# btretro_main.net
KiCad netlist of a schematic drawn in Altium Designer
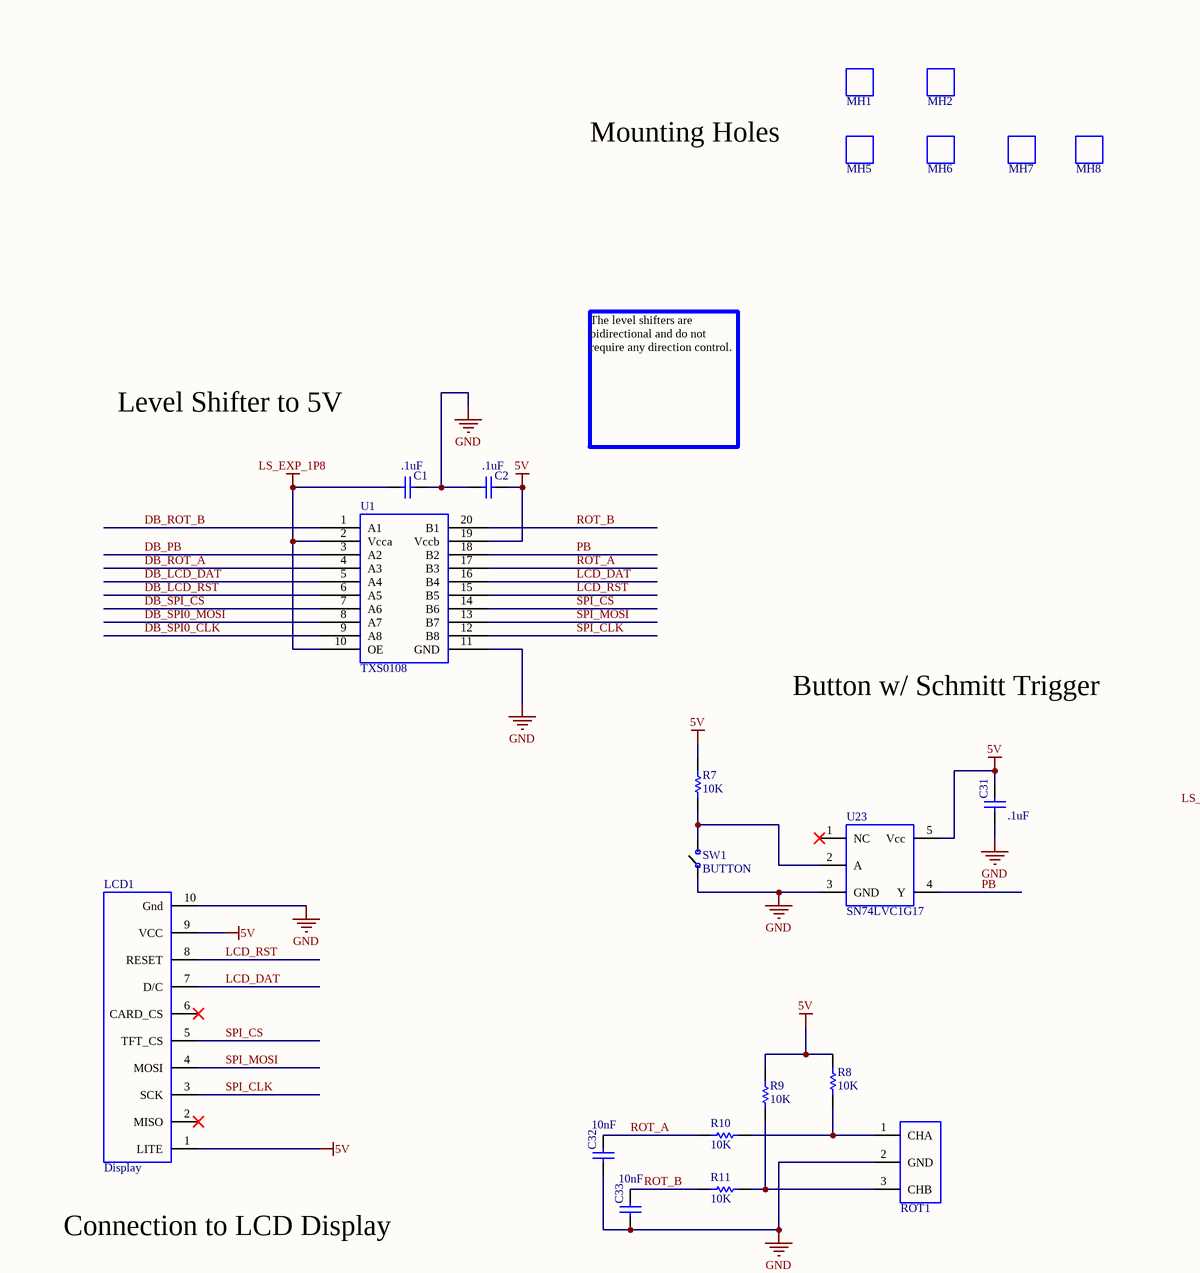
[diagram p0: btretro_main.SchDoc, top left]
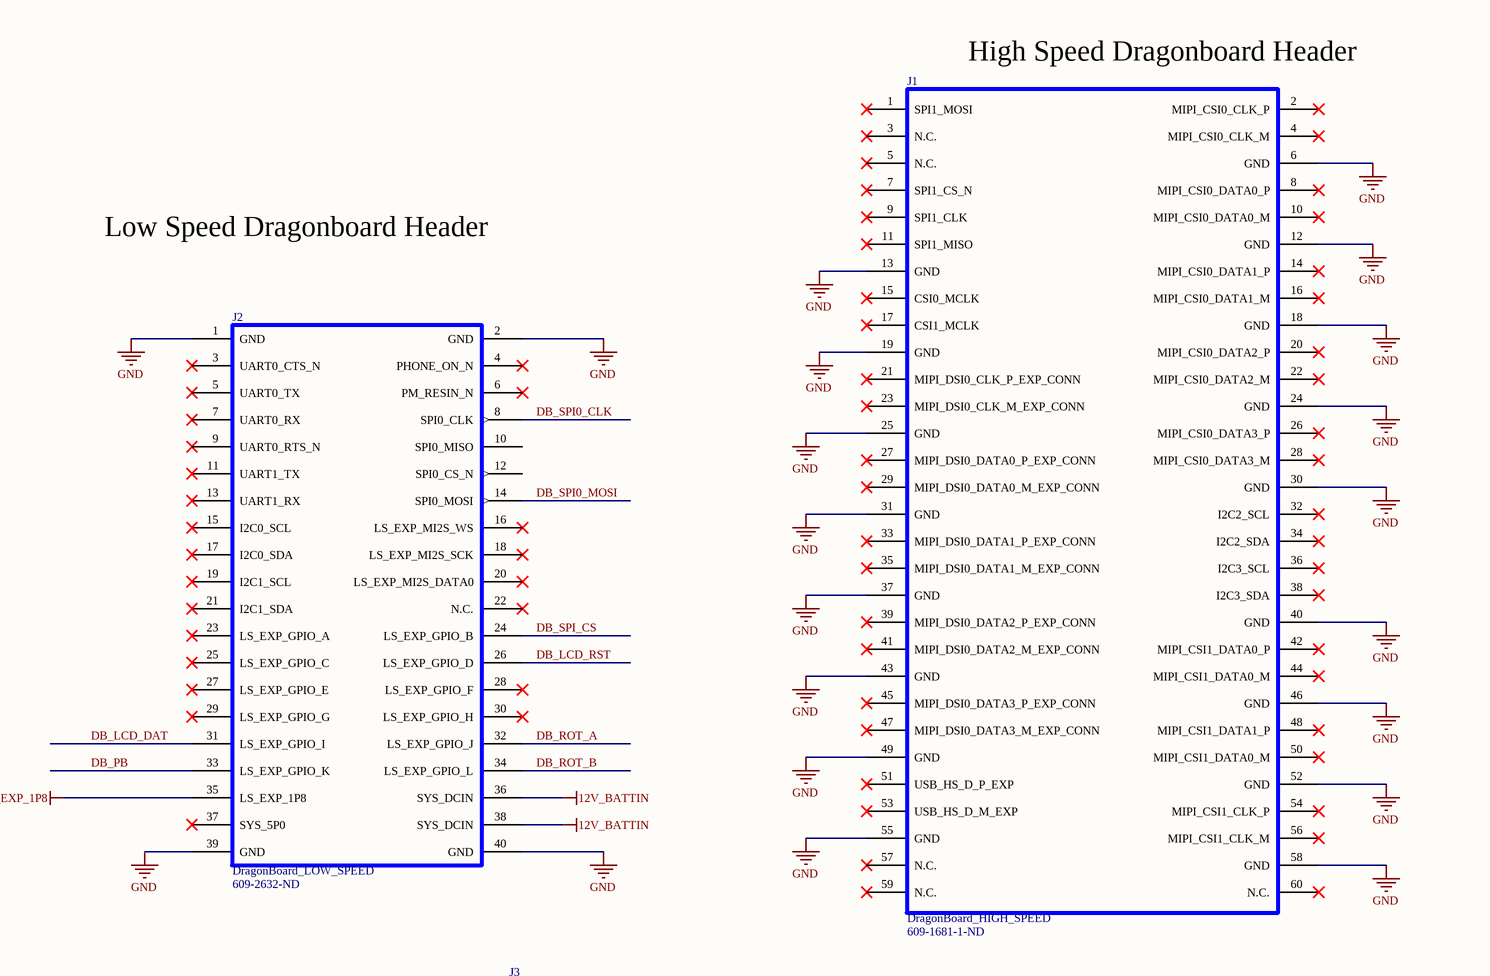
[diagram p1: btretro_main.SchDoc, top right]
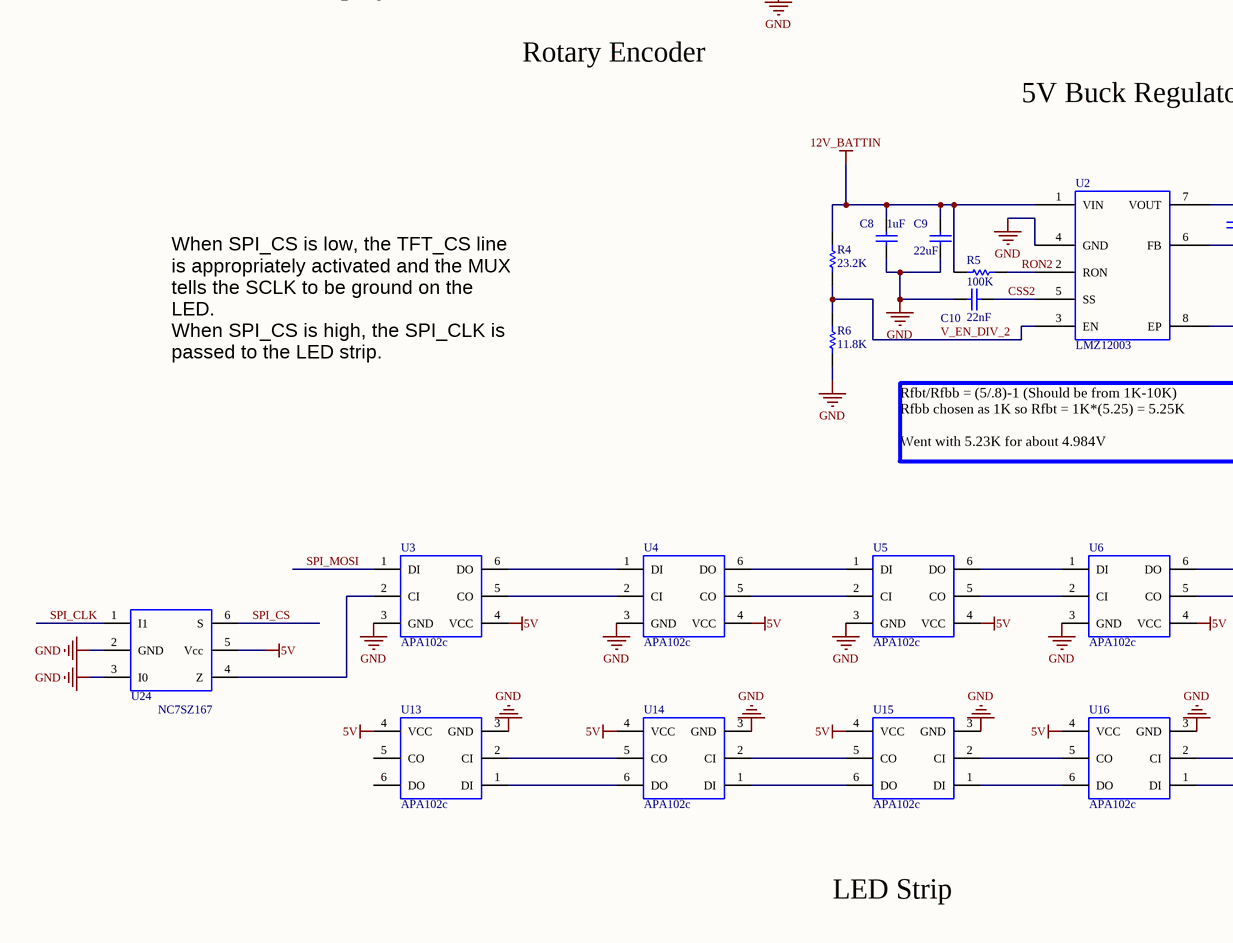
[diagram p2: btretro_main.SchDoc, bottom left]
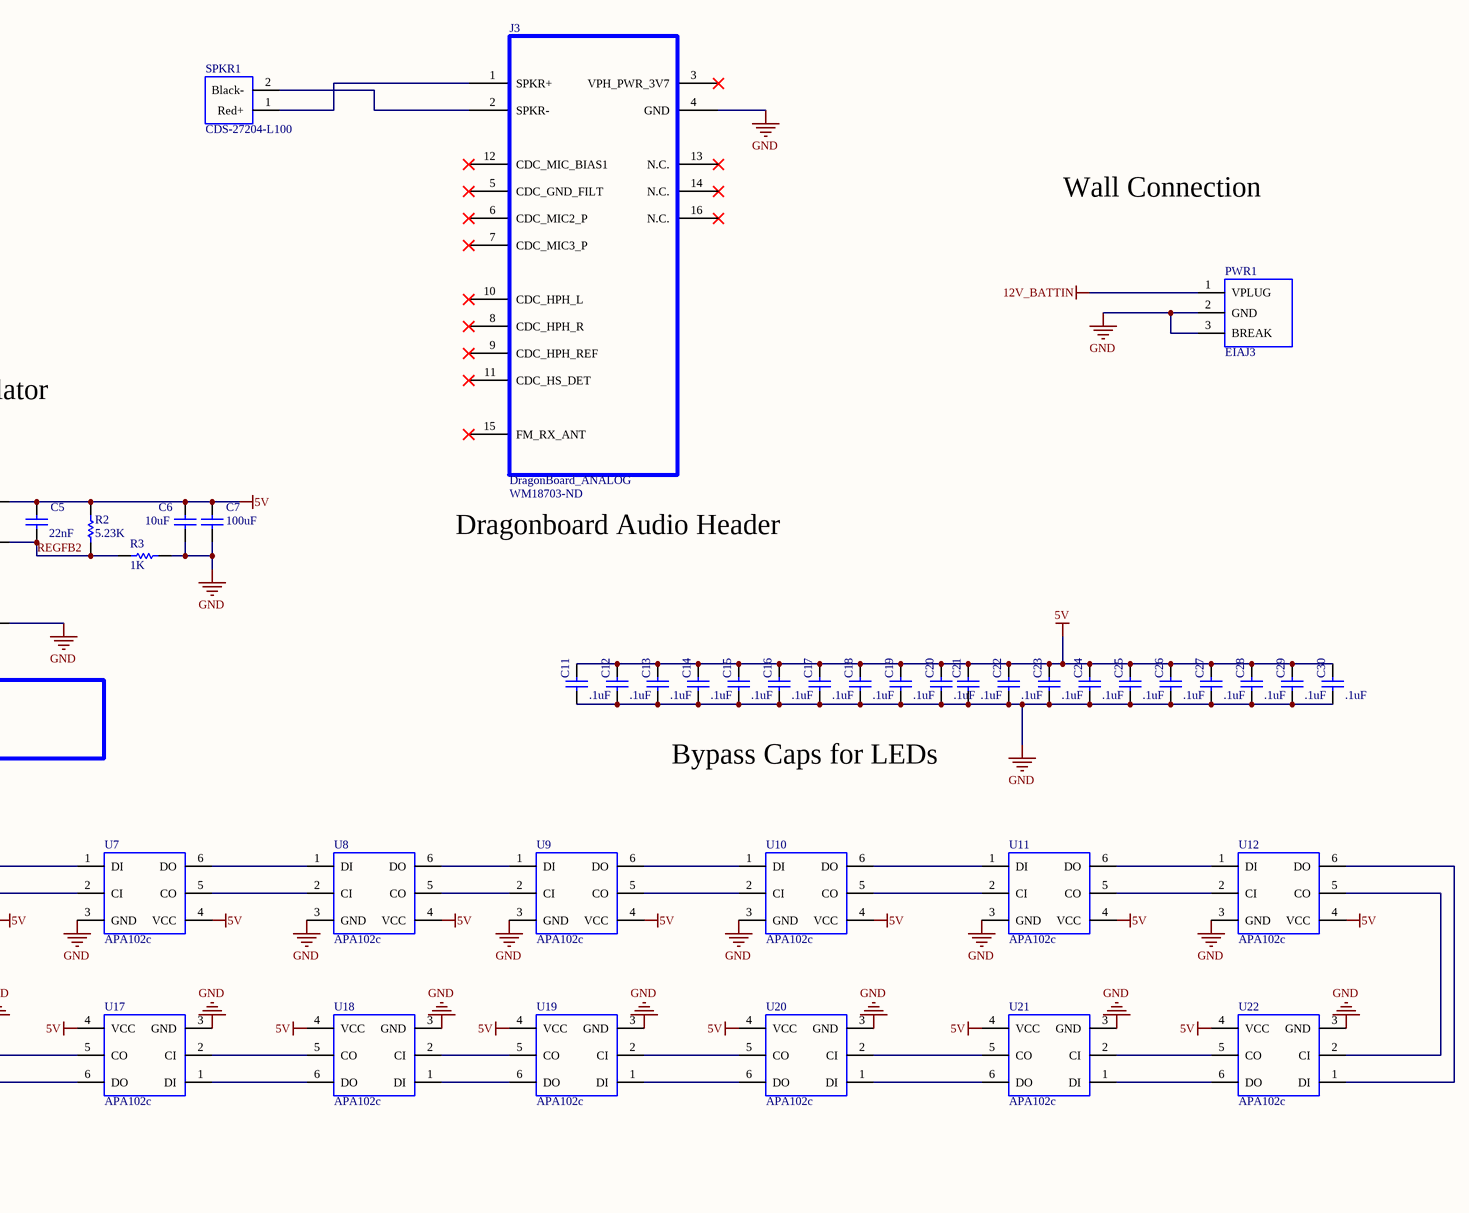
[diagram p3: btretro_main.SchDoc, bottom right]

(export (version "E")
  (design (tool "Eeschema 10.0.6"))
  (components
    (comp (ref "C1")
      (value ".1uF")
      (footprint "CAPC2012X135N")
      (description "Cap Ceramic 0.1uF 250V X7T 10% SMD 0805 125C Plastic T/R")
      (fields
        (field (name "MANUFACTURER") "TDK")
        (field (name "MANUFACTURER PART NUMBER") "C2012X7T2E104K125AE")
      )
      (libsource (lib "schlib_truman") (part "CAP_0805_.1u_250V"))
    )
    (comp (ref "C2")
      (value ".1uF")
      (footprint "CAPC2012X135N")
      (description "Cap Ceramic 0.1uF 250V X7T 10% SMD 0805 125C Plastic T/R")
      (fields
        (field (name "MANUFACTURER") "TDK")
        (field (name "MANUFACTURER PART NUMBER") "C2012X7T2E104K125AE")
      )
      (libsource (lib "schlib_truman") (part "CAP_0805_.1u_250V"))
    )
    (comp (ref "C5")
      (value "22nF")
      (footprint "CAPC2012X135N")
      (description "CAP CER 0.022UF 100V X7R 0805")
      (fields
        (field (name "MANUFACTURER") "TDK")
        (field (name "MANUFACTURER PART NUMBER") "CGJ4J2X7R2A223K125AA")
      )
      (libsource (lib "schlib_truman") (part "CAP_0805_22n_100V"))
    )
    (comp (ref "C6")
      (value "10uF")
      (footprint "CAPC2012X135N")
      (description "Cap Ceramic 10uF 16V X5R 10% SMD 0805 85C T/R")
      (fields
        (field (name "MANUFACTURER") "Johanson Dielectrics")
        (field (name "MANUFACTURER PART NUMBER") "160R15X106KV4E")
      )
      (libsource (lib "schlib_truman") (part "CAP_0805_10u_16V"))
    )
    (comp (ref "C7")
      (value "100uF")
      (footprint "FP_1210")
      (description "Cap Ceramic 100uF 10V X5R 20% SMD 1210 85C Embossed T/R")
      (fields
        (field (name "MANUFACTURER") "Murata")
        (field (name "MANUFACTURER PART NUMBER") "GRM32ER61A107ME20L")
      )
      (libsource (lib "schlib_truman") (part "CAP_1210_100u_10V"))
    )
    (comp (ref "C8")
      (value "1uF")
      (footprint "CAPC2012X135N")
      (description "CAP CER 1UF 100V X7S 0805")
      (fields
        (field (name "MANUFACTURER") "TDK")
        (field (name "MANUFACTURER PART NUMBER") "C2012X7S2A105K125AE")
      )
      (libsource (lib "schlib_truman") (part "CAP_0805_1u_100V"))
    )
    (comp (ref "C9")
      (value "22uF")
      (footprint "CAPC2012X135N")
      (fields
        (field (name "MANUFACTURER") "Samsung")
        (field (name "MANUFACTURER PART NUMBER") "CL21A226MAQNNNE")
        (field (name "TOLERANCE") "20%")
      )
      (libsource (lib "schlib_truman") (part "CAP_0805_22u_25V"))
    )
    (comp (ref "C10")
      (value "22nF")
      (footprint "CAPC2012X135N")
      (description "CAP CER 0.022UF 100V X7R 0805")
      (fields
        (field (name "MANUFACTURER") "TDK")
        (field (name "MANUFACTURER PART NUMBER") "CGJ4J2X7R2A223K125AA")
      )
      (libsource (lib "schlib_truman") (part "CAP_0805_22n_100V"))
    )
    (comp (ref "C11")
      (value ".1uF")
      (footprint "CAPC2012X135N")
      (description "Cap Ceramic 0.1uF 250V X7T 10% SMD 0805 125C Plastic T/R")
      (fields
        (field (name "MANUFACTURER") "TDK")
        (field (name "MANUFACTURER PART NUMBER") "C2012X7T2E104K125AE")
      )
      (libsource (lib "btretro_schlib") (part "CAP_0805_.1u_250V"))
    )
    (comp (ref "C12")
      (value ".1uF")
      (footprint "CAPC2012X135N")
      (description "Cap Ceramic 0.1uF 250V X7T 10% SMD 0805 125C Plastic T/R")
      (fields
        (field (name "MANUFACTURER") "TDK")
        (field (name "MANUFACTURER PART NUMBER") "C2012X7T2E104K125AE")
      )
      (libsource (lib "btretro_schlib") (part "CAP_0805_.1u_250V"))
    )
    (comp (ref "C13")
      (value ".1uF")
      (footprint "CAPC2012X135N")
      (description "Cap Ceramic 0.1uF 250V X7T 10% SMD 0805 125C Plastic T/R")
      (fields
        (field (name "MANUFACTURER") "TDK")
        (field (name "MANUFACTURER PART NUMBER") "C2012X7T2E104K125AE")
      )
      (libsource (lib "btretro_schlib") (part "CAP_0805_.1u_250V"))
    )
    (comp (ref "C14")
      (value ".1uF")
      (footprint "CAPC2012X135N")
      (description "Cap Ceramic 0.1uF 250V X7T 10% SMD 0805 125C Plastic T/R")
      (fields
        (field (name "MANUFACTURER") "TDK")
        (field (name "MANUFACTURER PART NUMBER") "C2012X7T2E104K125AE")
      )
      (libsource (lib "btretro_schlib") (part "CAP_0805_.1u_250V"))
    )
    (comp (ref "C15")
      (value ".1uF")
      (footprint "CAPC2012X135N")
      (description "Cap Ceramic 0.1uF 250V X7T 10% SMD 0805 125C Plastic T/R")
      (fields
        (field (name "MANUFACTURER") "TDK")
        (field (name "MANUFACTURER PART NUMBER") "C2012X7T2E104K125AE")
      )
      (libsource (lib "btretro_schlib") (part "CAP_0805_.1u_250V"))
    )
    (comp (ref "C16")
      (value ".1uF")
      (footprint "CAPC2012X135N")
      (description "Cap Ceramic 0.1uF 250V X7T 10% SMD 0805 125C Plastic T/R")
      (fields
        (field (name "MANUFACTURER") "TDK")
        (field (name "MANUFACTURER PART NUMBER") "C2012X7T2E104K125AE")
      )
      (libsource (lib "btretro_schlib") (part "CAP_0805_.1u_250V"))
    )
    (comp (ref "C17")
      (value ".1uF")
      (footprint "CAPC2012X135N")
      (description "Cap Ceramic 0.1uF 250V X7T 10% SMD 0805 125C Plastic T/R")
      (fields
        (field (name "MANUFACTURER") "TDK")
        (field (name "MANUFACTURER PART NUMBER") "C2012X7T2E104K125AE")
      )
      (libsource (lib "btretro_schlib") (part "CAP_0805_.1u_250V"))
    )
    (comp (ref "C18")
      (value ".1uF")
      (footprint "CAPC2012X135N")
      (description "Cap Ceramic 0.1uF 250V X7T 10% SMD 0805 125C Plastic T/R")
      (fields
        (field (name "MANUFACTURER") "TDK")
        (field (name "MANUFACTURER PART NUMBER") "C2012X7T2E104K125AE")
      )
      (libsource (lib "btretro_schlib") (part "CAP_0805_.1u_250V"))
    )
    (comp (ref "C19")
      (value ".1uF")
      (footprint "CAPC2012X135N")
      (description "Cap Ceramic 0.1uF 250V X7T 10% SMD 0805 125C Plastic T/R")
      (fields
        (field (name "MANUFACTURER") "TDK")
        (field (name "MANUFACTURER PART NUMBER") "C2012X7T2E104K125AE")
      )
      (libsource (lib "btretro_schlib") (part "CAP_0805_.1u_250V"))
    )
    (comp (ref "C20")
      (value ".1uF")
      (footprint "CAPC2012X135N")
      (description "Cap Ceramic 0.1uF 250V X7T 10% SMD 0805 125C Plastic T/R")
      (fields
        (field (name "MANUFACTURER") "TDK")
        (field (name "MANUFACTURER PART NUMBER") "C2012X7T2E104K125AE")
      )
      (libsource (lib "btretro_schlib") (part "CAP_0805_.1u_250V"))
    )
    (comp (ref "C21")
      (value ".1uF")
      (footprint "CAPC2012X135N")
      (description "Cap Ceramic 0.1uF 250V X7T 10% SMD 0805 125C Plastic T/R")
      (fields
        (field (name "MANUFACTURER") "TDK")
        (field (name "MANUFACTURER PART NUMBER") "C2012X7T2E104K125AE")
      )
      (libsource (lib "btretro_schlib") (part "CAP_0805_.1u_250V"))
    )
    (comp (ref "C22")
      (value ".1uF")
      (footprint "CAPC2012X135N")
      (description "Cap Ceramic 0.1uF 250V X7T 10% SMD 0805 125C Plastic T/R")
      (fields
        (field (name "MANUFACTURER") "TDK")
        (field (name "MANUFACTURER PART NUMBER") "C2012X7T2E104K125AE")
      )
      (libsource (lib "btretro_schlib") (part "CAP_0805_.1u_250V"))
    )
    (comp (ref "C23")
      (value ".1uF")
      (footprint "CAPC2012X135N")
      (description "Cap Ceramic 0.1uF 250V X7T 10% SMD 0805 125C Plastic T/R")
      (fields
        (field (name "MANUFACTURER") "TDK")
        (field (name "MANUFACTURER PART NUMBER") "C2012X7T2E104K125AE")
      )
      (libsource (lib "btretro_schlib") (part "CAP_0805_.1u_250V"))
    )
    (comp (ref "C24")
      (value ".1uF")
      (footprint "CAPC2012X135N")
      (description "Cap Ceramic 0.1uF 250V X7T 10% SMD 0805 125C Plastic T/R")
      (fields
        (field (name "MANUFACTURER") "TDK")
        (field (name "MANUFACTURER PART NUMBER") "C2012X7T2E104K125AE")
      )
      (libsource (lib "btretro_schlib") (part "CAP_0805_.1u_250V"))
    )
    (comp (ref "C25")
      (value ".1uF")
      (footprint "CAPC2012X135N")
      (description "Cap Ceramic 0.1uF 250V X7T 10% SMD 0805 125C Plastic T/R")
      (fields
        (field (name "MANUFACTURER") "TDK")
        (field (name "MANUFACTURER PART NUMBER") "C2012X7T2E104K125AE")
      )
      (libsource (lib "btretro_schlib") (part "CAP_0805_.1u_250V"))
    )
    (comp (ref "C26")
      (value ".1uF")
      (footprint "CAPC2012X135N")
      (description "Cap Ceramic 0.1uF 250V X7T 10% SMD 0805 125C Plastic T/R")
      (fields
        (field (name "MANUFACTURER") "TDK")
        (field (name "MANUFACTURER PART NUMBER") "C2012X7T2E104K125AE")
      )
      (libsource (lib "btretro_schlib") (part "CAP_0805_.1u_250V"))
    )
    (comp (ref "C27")
      (value ".1uF")
      (footprint "CAPC2012X135N")
      (description "Cap Ceramic 0.1uF 250V X7T 10% SMD 0805 125C Plastic T/R")
      (fields
        (field (name "MANUFACTURER") "TDK")
        (field (name "MANUFACTURER PART NUMBER") "C2012X7T2E104K125AE")
      )
      (libsource (lib "btretro_schlib") (part "CAP_0805_.1u_250V"))
    )
    (comp (ref "C28")
      (value ".1uF")
      (footprint "CAPC2012X135N")
      (description "Cap Ceramic 0.1uF 250V X7T 10% SMD 0805 125C Plastic T/R")
      (fields
        (field (name "MANUFACTURER") "TDK")
        (field (name "MANUFACTURER PART NUMBER") "C2012X7T2E104K125AE")
      )
      (libsource (lib "btretro_schlib") (part "CAP_0805_.1u_250V"))
    )
    (comp (ref "C29")
      (value ".1uF")
      (footprint "CAPC2012X135N")
      (description "Cap Ceramic 0.1uF 250V X7T 10% SMD 0805 125C Plastic T/R")
      (fields
        (field (name "MANUFACTURER") "TDK")
        (field (name "MANUFACTURER PART NUMBER") "C2012X7T2E104K125AE")
      )
      (libsource (lib "btretro_schlib") (part "CAP_0805_.1u_250V"))
    )
    (comp (ref "C30")
      (value ".1uF")
      (footprint "CAPC2012X135N")
      (description "Cap Ceramic 0.1uF 250V X7T 10% SMD 0805 125C Plastic T/R")
      (fields
        (field (name "MANUFACTURER") "TDK")
        (field (name "MANUFACTURER PART NUMBER") "C2012X7T2E104K125AE")
      )
      (libsource (lib "btretro_schlib") (part "CAP_0805_.1u_250V"))
    )
    (comp (ref "C31")
      (value ".1uF")
      (footprint "CAPC2012X135N")
      (description "Cap Ceramic 0.1uF 250V X7T 10% SMD 0805 125C Plastic T/R")
      (fields
        (field (name "MANUFACTURER") "TDK")
        (field (name "MANUFACTURER PART NUMBER") "C2012X7T2E104K125AE")
      )
      (libsource (lib "btretro_schlib") (part "CAP_0805_.1u_250V"))
    )
    (comp (ref "C32")
      (value "CAP_0805_10n_250V")
      (footprint "CAPC2012X135N")
      (description "Cap Ceramic 0.1uF 250V X7T 10% SMD 0805 125C Plastic T/R")
      (fields
        (field (name "CAPACITANCE") "10nF")
        (field (name "MANUFACTURER") "TDK")
        (field (name "MANUFACTURER PART NUMBER") "C2012X7R2E103K125AA")
      )
      (libsource (lib "btretro_schlib") (part "CAP_0805_10n_250V"))
    )
    (comp (ref "C33")
      (value "CAP_0805_10n_250V")
      (footprint "CAPC2012X135N")
      (description "Cap Ceramic 0.1uF 250V X7T 10% SMD 0805 125C Plastic T/R")
      (fields
        (field (name "CAPACITANCE") "10nF")
        (field (name "MANUFACTURER") "TDK")
        (field (name "MANUFACTURER PART NUMBER") "C2012X7R2E103K125AA")
      )
      (libsource (lib "btretro_schlib") (part "CAP_0805_10n_250V"))
    )
    (comp (ref "J1")
      (value "DragonBoard_HIGH_SPEED")
      (footprint "DB_HIGH_SPEED")
      (description "60 Position Connector Plug, Center Strip Contacts Surface Mount Gold")
      (fields
        (field (name "MANUFACTURER") "Amphenol FCI")
        (field (name "MANUFACTURER PART NUMBER") "61083-064402LF")
        (field (name "SUPPLIER PART NUMBER 1") "609-1681-1-ND")
      )
      (libsource (lib "schlib_truman") (part "DragonBoard_HIGH_SPEED"))
    )
    (comp (ref "J2")
      (value "DragonBoard_LOW_SPEED")
      (footprint "57202_40_PIN_HEADER")
      (description "40 Positions Header, Unshrouded Connector 0.079\" (2.00mm) Surface Mount Gold, GXT™")
      (fields
        (field (name "MANUFACTURER") "Amphenol FCI")
        (field (name "MANUFACTURER PART NUMBER") "57202-G52-20LF")
        (field (name "SUPPLIER PART NUMBER 1") "609-2632-ND")
      )
      (libsource (lib "btretro_schlib") (part "DragonBoard_LOW_SPEED"))
    )
    (comp (ref "J3")
      (value "DragonBoard_ANALOG")
      (footprint "16_PIN_ANALOG_CONN")
      (description "Conn Socket Strip RCP 16 POS 2mm Solder ST SMD Tube")
      (fields
        (field (name "MANUFACTURER") "Molex")
        (field (name "MANUFACTURER PART NUMBER") "0791091007")
        (field (name "SUPPLIER PART NUMBER 1") "WM18703-ND")
      )
      (libsource (lib "schlib_truman") (part "DragonBoard_ANALOG"))
    )
    (comp (ref "LCD1")
      (value "Display")
      (footprint "LCD_HOLES")
      (description "TFT Display")
      (libsource (lib "btretro_schlib") (part "LCD_SCREEN_BTRETRO"))
    )
    (comp (ref "MH1")
      (value "MOUNTHOLES")
      (footprint "HOLE_BTRETRO")
      (description "HOLE")
      (libsource (lib "btretro_schlib") (part "MOUNTHOLES"))
    )
    (comp (ref "MH2")
      (value "MOUNTHOLES")
      (footprint "HOLE_BTRETRO")
      (description "HOLE")
      (libsource (lib "btretro_schlib") (part "MOUNTHOLES"))
    )
    (comp (ref "MH5")
      (value "MOUNTHOLES")
      (footprint "HOLE_BTRETRO")
      (description "HOLE")
      (libsource (lib "btretro_schlib") (part "MOUNTHOLES"))
    )
    (comp (ref "MH6")
      (value "MOUNTHOLES")
      (footprint "HOLE_BTRETRO")
      (description "HOLE")
      (libsource (lib "btretro_schlib") (part "MOUNTHOLES"))
    )
    (comp (ref "MH7")
      (value "MOUNTHOLES")
      (footprint "HOLE_BTRETRO")
      (description "HOLE")
      (libsource (lib "btretro_schlib") (part "MOUNTHOLES"))
    )
    (comp (ref "MH8")
      (value "MOUNTHOLES")
      (footprint "HOLE_BTRETRO")
      (description "HOLE")
      (libsource (lib "btretro_schlib") (part "MOUNTHOLES"))
    )
    (comp (ref "PWR1")
      (value "EIAJ3")
      (footprint "EIAJ3 BARREL")
      (description "PJ1-021 Series 1.65 mm x 5.15 mm 16 V Right Angle SMT Power Jack")
      (fields (field (name "MANUFACTURER") "CUI") (field (name "MANUFACTURER PART NUMBER") "PJ1-021-SMT-TR"))
      (libsource (lib "btretro_schlib") (part "EIAJ3"))
    )
    (comp (ref "R2")
      (value "RES_5.23K")
      (footprint "RES0805")
      (description "Thick Film Resistors 5.23K OHM 1%")
      (fields
        (field (name "MANUFACTURER") "Yageo")
        (field (name "MANUFACTURER PART NUMBER") "RC0805FR-075K23L")
        (field (name "ALTIUM_UNNAMED_1") "5.23K")
      )
      (libsource (lib "schlib_truman") (part "RES_0805_5.23K"))
    )
    (comp (ref "R3")
      (value "RES_0805_1K")
      (footprint "RES0805")
      (description "RES SMD 1K OHM 1% 1/8W 0805")
      (fields
        (field (name "MANUFACTURER") "Yageo")
        (field (name "MANUFACTURER PART NUMBER") "RC0805FR-071KL")
        (field (name "ALTIUM_UNNAMED_1") "1K")
      )
      (libsource (lib "schlib_truman") (part "RES_0805_1K"))
    )
    (comp (ref "R4")
      (value "RES_0805_23.2K")
      (footprint "RES0805")
      (description "RESISTOR, THICK FILM, 23.2KOHM, 125mW, ± 1%")
      (fields
        (field (name "MANUFACTURER") "Panasonic ECG")
        (field (name "MANUFACTURER PART NUMBER") "ERJ-6ENF2322V")
        (field (name "ALTIUM_UNNAMED_1") "23.2K")
      )
      (libsource (lib "schlib_truman") (part "RES_0805_23.2K"))
    )
    (comp (ref "R5")
      (value "RES_0805_100K")
      (footprint "RES0805")
      (description "Res Thick Film 0805 100K Ohm 1% 0.125W(1/8W) ±100ppm/C Molded SMD Automotive Punched T/R")
      (fields
        (field (name "MANUFACTURER") "Panasonic ECG")
        (field (name "MANUFACTURER PART NUMBER") "ERJ-6ENF1003V")
        (field (name "ALTIUM_UNNAMED_1") "100K")
      )
      (libsource (lib "schlib_truman") (part "RES_0805_100K"))
    )
    (comp (ref "R6")
      (value "RES_0805_11.8K")
      (footprint "RES0805")
      (description "RES SMD 11.8K OHM 1% 1/8W 0805")
      (fields
        (field (name "MANUFACTURER") "Yageo")
        (field (name "MANUFACTURER PART NUMBER") "RC0805FR-0711K8L")
        (field (name "ALTIUM_UNNAMED_1") "11.8K")
      )
      (libsource (lib "schlib_truman") (part "RES_0805_11.8K"))
    )
    (comp (ref "R7")
      (value "RES_0805_10K")
      (footprint "RES0805")
      (description "RES, THICK FILM, 10K, 5%, 0.125W, 0805")
      (fields
        (field (name "MANUFACTURER") "Yageo")
        (field (name "MANUFACTURER PART NUMBER") "RC0805JR-0710KL")
        (field (name "RESISTANCE") "10K")
      )
      (libsource (lib "btretro_schlib") (part "RES_0805_10K"))
    )
    (comp (ref "R8")
      (value "RES_0805_10K")
      (footprint "RES0805")
      (description "RES, THICK FILM, 10K, 5%, 0.125W, 0805")
      (fields
        (field (name "MANUFACTURER") "Yageo")
        (field (name "MANUFACTURER PART NUMBER") "RC0805JR-0710KL")
        (field (name "RESISTANCE") "10K")
      )
      (libsource (lib "btretro_schlib") (part "RES_0805_10K"))
    )
    (comp (ref "R9")
      (value "RES_0805_10K")
      (footprint "RES0805")
      (description "RES, THICK FILM, 10K, 5%, 0.125W, 0805")
      (fields
        (field (name "MANUFACTURER") "Yageo")
        (field (name "MANUFACTURER PART NUMBER") "RC0805JR-0710KL")
        (field (name "RESISTANCE") "10K")
      )
      (libsource (lib "btretro_schlib") (part "RES_0805_10K"))
    )
    (comp (ref "R10")
      (value "RES_0805_10K")
      (footprint "RES0805")
      (description "RES, THICK FILM, 10K, 5%, 0.125W, 0805")
      (fields
        (field (name "MANUFACTURER") "Yageo")
        (field (name "MANUFACTURER PART NUMBER") "RC0805JR-0710KL")
        (field (name "RESISTANCE") "10K")
      )
      (libsource (lib "btretro_schlib") (part "RES_0805_10K"))
    )
    (comp (ref "R11")
      (value "RES_0805_10K")
      (footprint "RES0805")
      (description "RES, THICK FILM, 10K, 5%, 0.125W, 0805")
      (fields
        (field (name "MANUFACTURER") "Yageo")
        (field (name "MANUFACTURER PART NUMBER") "RC0805JR-0710KL")
        (field (name "RESISTANCE") "10K")
      )
      (libsource (lib "btretro_schlib") (part "RES_0805_10K"))
    )
    (comp (ref "ROT1")
      (value "ROT_ENCODER")
      (footprint "ROTENCFP")
      (description "Encoders 15mm SHAFT w/SWITCH")
      (fields
        (field (name "MANUFACTURER") "Bourns")
        (field (name "MANUFACTURER PART NUMBER") "PEC11R-4015F-S0024")
      )
      (libsource (lib "btretro_schlib") (part "ROT_ENCODER"))
    )
    (comp (ref "SPKR1")
      (value "CDS-27204-L100")
      (footprint "SPK_BTRETRO")
      (description "4 Ohm Magnetic Speaker 2W 20Hz ~ 20kHz Top Rectangular 93dB")
      (fields (field (name "MANUFACTURER") "CUI") (field (name "VOLTAGE") "300V"))
      (libsource (lib "btretro_schlib") (part "CDS-27204-L100"))
    )
    (comp (ref "SW1")
      (value "BUTTON")
      (footprint "BUTTON")
      (description "...It's a button!")
      (libsource (lib "btretro_schlib") (part "BUTTON"))
    )
    (comp (ref "U1")
      (value "TXS0108")
      (footprint "TSSOP20")
      (description "TRANSLATOR, VOLTAGE, 8BIT, 20TSSOP")
      (fields
        (field (name "MANUFACTURER") "Texas Instruments")
        (field (name "MANUFACTURER PART NUMBER") "TXS0108EPWR")
      )
      (libsource (lib "schlib_truman") (part "TXS0108"))
    )
    (comp (ref "U2")
      (value "LMZ12003")
      (footprint "TO-PMOD-7")
      (description "POWER MODULE, TO-PMOD-7, FULL REEL")
      (fields
        (field (name "MANUFACTURER") "Texas Instruments")
        (field (name "MANUFACTURER PART NUMBER") "LMZ12003TZ-ADJ/NOPB")
      )
      (libsource (lib "schlib_truman") (part "LMZ12003"))
    )
    (comp (ref "U3")
      (value "APA102c")
      (footprint "LED_APA")
      (description "SPI LED")
      (libsource (lib "") (part "APA102_1"))
    )
    (comp (ref "U4")
      (value "APA102c")
      (footprint "LED_APA")
      (description "SPI LED")
      (libsource (lib "") (part "APA102_1"))
    )
    (comp (ref "U5")
      (value "APA102c")
      (footprint "LED_APA")
      (description "SPI LED")
      (libsource (lib "") (part "APA102_1"))
    )
    (comp (ref "U6")
      (value "APA102c")
      (footprint "LED_APA")
      (description "SPI LED")
      (libsource (lib "") (part "APA102_1"))
    )
    (comp (ref "U7")
      (value "APA102c")
      (footprint "LED_APA")
      (description "SPI LED")
      (libsource (lib "") (part "APA102_1"))
    )
    (comp (ref "U8")
      (value "APA102c")
      (footprint "LED_APA")
      (description "SPI LED")
      (libsource (lib "") (part "APA102_1"))
    )
    (comp (ref "U9")
      (value "APA102c")
      (footprint "LED_APA")
      (description "SPI LED")
      (libsource (lib "") (part "APA102_1"))
    )
    (comp (ref "U10")
      (value "APA102c")
      (footprint "LED_APA")
      (description "SPI LED")
      (libsource (lib "") (part "APA102_1"))
    )
    (comp (ref "U11")
      (value "APA102c")
      (footprint "LED_APA")
      (description "SPI LED")
      (libsource (lib "") (part "APA102_1"))
    )
    (comp (ref "U12")
      (value "APA102c")
      (footprint "LED_APA")
      (description "SPI LED")
      (libsource (lib "") (part "APA102_1"))
    )
    (comp (ref "U13")
      (value "APA102c")
      (footprint "LED_APA")
      (description "SPI LED")
      (libsource (lib "btretro_schlib") (part "APA102"))
    )
    (comp (ref "U14")
      (value "APA102c")
      (footprint "LED_APA")
      (description "SPI LED")
      (libsource (lib "btretro_schlib") (part "APA102"))
    )
    (comp (ref "U15")
      (value "APA102c")
      (footprint "LED_APA")
      (description "SPI LED")
      (libsource (lib "btretro_schlib") (part "APA102"))
    )
    (comp (ref "U16")
      (value "APA102c")
      (footprint "LED_APA")
      (description "SPI LED")
      (libsource (lib "btretro_schlib") (part "APA102"))
    )
    (comp (ref "U17")
      (value "APA102c")
      (footprint "LED_APA")
      (description "SPI LED")
      (libsource (lib "btretro_schlib") (part "APA102"))
    )
    (comp (ref "U18")
      (value "APA102c")
      (footprint "LED_APA")
      (description "SPI LED")
      (libsource (lib "btretro_schlib") (part "APA102"))
    )
    (comp (ref "U19")
      (value "APA102c")
      (footprint "LED_APA")
      (description "SPI LED")
      (libsource (lib "btretro_schlib") (part "APA102"))
    )
    (comp (ref "U20")
      (value "APA102c")
      (footprint "LED_APA")
      (description "SPI LED")
      (libsource (lib "btretro_schlib") (part "APA102"))
    )
    (comp (ref "U21")
      (value "APA102c")
      (footprint "LED_APA")
      (description "SPI LED")
      (libsource (lib "btretro_schlib") (part "APA102"))
    )
    (comp (ref "U22")
      (value "APA102c")
      (footprint "LED_APA")
      (description "SPI LED")
      (libsource (lib "btretro_schlib") (part "APA102"))
    )
    (comp (ref "U23")
      (value "SN74LVC1G17")
      (footprint "DBV0005A (SOT-23)")
      (description "IC BUFFER SCHMIT TRIG SOT23-5")
      (fields
        (field (name "MANUFACTURER") "Texas Instruments")
        (field (name "MANUFACTURER PART NUMBER") "SN74LVC1G17DBVR")
      )
      (libsource (lib "btretro_schlib") (part "SN74LVC1G17"))
    )
    (comp (ref "U24")
      (value "NC7SZ167")
      (footprint "SC70")
      (description "FAIRCHILD SEMICONDUCTOR         NC7SZ157P6X             Logic Type:Multiplexer")
      (fields
        (field (name "MANUFACTURER") "Fairchild Semiconductor")
        (field (name "MANUFACTURER PART NUMBER") "NC7SZ157P6X")
      )
      (libsource (lib "btretro_schlib") (part "NC7SZ157"))
    )
  )
  (nets
    (net (code "1") (name "/CSS2") (class "Default")
      (node (ref "C10") (pin "2") (pinfunction "2_2") (pintype "passive"))
      (node (ref "U2") (pin "5") (pinfunction "SS_5") (pintype "passive"))
    )
    (net (code "2") (name "/DB_LCD_DAT") (class "Default")
      (node (ref "J2") (pin "31") (pinfunction "LS_EXP_GPIO_I_31") (pintype "passive"))
      (node (ref "U1") (pin "5") (pinfunction "A4_5") (pintype "passive"))
    )
    (net (code "3") (name "/DB_LCD_RST") (class "Default")
      (node (ref "J2") (pin "26") (pinfunction "LS_EXP_GPIO_D_26") (pintype "passive"))
      (node (ref "U1") (pin "6") (pinfunction "A5_6") (pintype "passive"))
    )
    (net (code "4") (name "/DB_PB") (class "Default")
      (node (ref "J2") (pin "33") (pinfunction "LS_EXP_GPIO_K_33") (pintype "passive"))
      (node (ref "U1") (pin "3") (pinfunction "A2_3") (pintype "passive"))
    )
    (net (code "5") (name "/DB_ROT_A") (class "Default")
      (node (ref "J2") (pin "32") (pinfunction "LS_EXP_GPIO_J_32") (pintype "passive"))
      (node (ref "U1") (pin "4") (pinfunction "A3_4") (pintype "passive"))
    )
    (net (code "6") (name "/DB_ROT_B") (class "Default")
      (node (ref "J2") (pin "34") (pinfunction "LS_EXP_GPIO_L_34") (pintype "passive"))
      (node (ref "U1") (pin "1") (pinfunction "A1_1") (pintype "passive"))
    )
    (net (code "7") (name "/DB_SPI0_CLK") (class "Default")
      (node (ref "J2") (pin "8") (pinfunction "SPI0_CLK_8") (pintype "output"))
      (node (ref "U1") (pin "9") (pinfunction "A8_9") (pintype "passive"))
    )
    (net (code "8") (name "/DB_SPI0_MOSI") (class "Default")
      (node (ref "J2") (pin "14") (pinfunction "SPI0_MOSI_14") (pintype "output"))
      (node (ref "U1") (pin "8") (pinfunction "A7_8") (pintype "passive"))
    )
    (net (code "9") (name "/DB_SPI_CS") (class "Default")
      (node (ref "J2") (pin "24") (pinfunction "LS_EXP_GPIO_B_24") (pintype "passive"))
      (node (ref "U1") (pin "7") (pinfunction "A6_7") (pintype "passive"))
    )
    (net (code "10") (name "/LCD_DAT") (class "Default")
      (node (ref "LCD1") (pin "7") (pinfunction "D/C_7") (pintype "passive"))
      (node (ref "U1") (pin "16") (pinfunction "B4_16") (pintype "passive"))
    )
    (net (code "11") (name "/LCD_RST") (class "Default")
      (node (ref "LCD1") (pin "8") (pinfunction "RESET_8") (pintype "passive"))
      (node (ref "U1") (pin "15") (pinfunction "B5_15") (pintype "passive"))
    )
    (net (code "12") (name "/PB") (class "Default")
      (node (ref "U1") (pin "18") (pinfunction "B2_18") (pintype "passive"))
      (node (ref "U23") (pin "4") (pinfunction "Y_4") (pintype "passive"))
    )
    (net (code "13") (name "/REGFB2") (class "Default")
      (node (ref "C5") (pin "1") (pinfunction "1_1") (pintype "passive"))
      (node (ref "R2") (pin "1") (pinfunction "1_1") (pintype "passive"))
      (node (ref "R3") (pin "1") (pinfunction "1_1") (pintype "passive"))
      (node (ref "U2") (pin "6") (pinfunction "FB_6") (pintype "passive"))
    )
    (net (code "14") (name "/RON2") (class "Default")
      (node (ref "R5") (pin "2") (pinfunction "2_2") (pintype "passive"))
      (node (ref "U2") (pin "2") (pinfunction "RON_2") (pintype "passive"))
    )
    (net (code "15") (name "/ROT_A") (class "Default")
      (node (ref "C32") (pin "2") (pinfunction "2_2") (pintype "passive"))
      (node (ref "R10") (pin "1") (pinfunction "1_1") (pintype "passive"))
      (node (ref "U1") (pin "17") (pinfunction "B3_17") (pintype "passive"))
    )
    (net (code "16") (name "/ROT_B") (class "Default")
      (node (ref "C33") (pin "2") (pinfunction "2_2") (pintype "passive"))
      (node (ref "R11") (pin "1") (pinfunction "1_1") (pintype "passive"))
      (node (ref "U1") (pin "20") (pinfunction "B1_20") (pintype "passive"))
    )
    (net (code "17") (name "/SPI_CLK") (class "Default")
      (node (ref "LCD1") (pin "3") (pinfunction "SCK_3") (pintype "passive"))
      (node (ref "U1") (pin "12") (pinfunction "B8_12") (pintype "passive"))
      (node (ref "U24") (pin "1") (pinfunction "I1_1") (pintype "passive"))
    )
    (net (code "18") (name "/SPI_CS") (class "Default")
      (node (ref "LCD1") (pin "5") (pinfunction "TFT_CS_5") (pintype "passive"))
      (node (ref "U1") (pin "14") (pinfunction "B6_14") (pintype "passive"))
      (node (ref "U24") (pin "6") (pinfunction "S_6") (pintype "passive"))
    )
    (net (code "19") (name "/SPI_MOSI") (class "Default")
      (node (ref "LCD1") (pin "4") (pinfunction "MOSI_4") (pintype "passive"))
      (node (ref "U1") (pin "13") (pinfunction "B7_13") (pintype "passive"))
      (node (ref "U3") (pin "1") (pinfunction "DI_1") (pintype "passive"))
    )
    (net (code "20") (name "/V_EN_DIV_2") (class "Default")
      (node (ref "R4") (pin "1") (pinfunction "1_1") (pintype "passive"))
      (node (ref "R6") (pin "2") (pinfunction "2_2") (pintype "passive"))
      (node (ref "U2") (pin "3") (pinfunction "EN_3") (pintype "passive"))
    )
    (net (code "21") (name "5V") (class "Default")
      (node (ref "C11") (pin "2") (pinfunction "2_2") (pintype "passive"))
      (node (ref "C12") (pin "2") (pinfunction "2_2") (pintype "passive"))
      (node (ref "C13") (pin "2") (pinfunction "2_2") (pintype "passive"))
      (node (ref "C14") (pin "2") (pinfunction "2_2") (pintype "passive"))
      (node (ref "C15") (pin "2") (pinfunction "2_2") (pintype "passive"))
      (node (ref "C16") (pin "2") (pinfunction "2_2") (pintype "passive"))
      (node (ref "C17") (pin "2") (pinfunction "2_2") (pintype "passive"))
      (node (ref "C18") (pin "2") (pinfunction "2_2") (pintype "passive"))
      (node (ref "C19") (pin "2") (pinfunction "2_2") (pintype "passive"))
      (node (ref "C2") (pin "2") (pinfunction "2_2") (pintype "passive"))
      (node (ref "C20") (pin "2") (pinfunction "2_2") (pintype "passive"))
      (node (ref "C21") (pin "2") (pinfunction "2_2") (pintype "passive"))
      (node (ref "C22") (pin "2") (pinfunction "2_2") (pintype "passive"))
      (node (ref "C23") (pin "2") (pinfunction "2_2") (pintype "passive"))
      (node (ref "C24") (pin "2") (pinfunction "2_2") (pintype "passive"))
      (node (ref "C25") (pin "2") (pinfunction "2_2") (pintype "passive"))
      (node (ref "C26") (pin "2") (pinfunction "2_2") (pintype "passive"))
      (node (ref "C27") (pin "2") (pinfunction "2_2") (pintype "passive"))
      (node (ref "C28") (pin "2") (pinfunction "2_2") (pintype "passive"))
      (node (ref "C29") (pin "2") (pinfunction "2_2") (pintype "passive"))
      (node (ref "C30") (pin "2") (pinfunction "2_2") (pintype "passive"))
      (node (ref "C31") (pin "2") (pinfunction "2_2") (pintype "passive"))
      (node (ref "C5") (pin "2") (pinfunction "2_2") (pintype "passive"))
      (node (ref "C6") (pin "2") (pinfunction "2_2") (pintype "passive"))
      (node (ref "C7") (pin "2") (pinfunction "2_2") (pintype "passive"))
      (node (ref "LCD1") (pin "1") (pinfunction "LITE_1") (pintype "passive"))
      (node (ref "LCD1") (pin "9") (pinfunction "VCC_9") (pintype "passive"))
      (node (ref "R2") (pin "2") (pinfunction "2_2") (pintype "passive"))
      (node (ref "R7") (pin "2") (pinfunction "2_2") (pintype "passive"))
      (node (ref "R8") (pin "2") (pinfunction "2_2") (pintype "passive"))
      (node (ref "R9") (pin "2") (pinfunction "2_2") (pintype "passive"))
      (node (ref "U1") (pin "19") (pinfunction "Vccb_19") (pintype "passive"))
      (node (ref "U10") (pin "4") (pinfunction "VCC_4") (pintype "passive"))
      (node (ref "U11") (pin "4") (pinfunction "VCC_4") (pintype "passive"))
      (node (ref "U12") (pin "4") (pinfunction "VCC_4") (pintype "passive"))
      (node (ref "U13") (pin "4") (pinfunction "VCC_4") (pintype "passive"))
      (node (ref "U14") (pin "4") (pinfunction "VCC_4") (pintype "passive"))
      (node (ref "U15") (pin "4") (pinfunction "VCC_4") (pintype "passive"))
      (node (ref "U16") (pin "4") (pinfunction "VCC_4") (pintype "passive"))
      (node (ref "U17") (pin "4") (pinfunction "VCC_4") (pintype "passive"))
      (node (ref "U18") (pin "4") (pinfunction "VCC_4") (pintype "passive"))
      (node (ref "U19") (pin "4") (pinfunction "VCC_4") (pintype "passive"))
      (node (ref "U2") (pin "7") (pinfunction "VOUT_7") (pintype "passive"))
      (node (ref "U20") (pin "4") (pinfunction "VCC_4") (pintype "passive"))
      (node (ref "U21") (pin "4") (pinfunction "VCC_4") (pintype "passive"))
      (node (ref "U22") (pin "4") (pinfunction "VCC_4") (pintype "passive"))
      (node (ref "U23") (pin "5") (pinfunction "Vcc_5") (pintype "passive"))
      (node (ref "U24") (pin "5") (pinfunction "Vcc_5") (pintype "passive"))
      (node (ref "U3") (pin "4") (pinfunction "VCC_4") (pintype "passive"))
      (node (ref "U4") (pin "4") (pinfunction "VCC_4") (pintype "passive"))
      (node (ref "U5") (pin "4") (pinfunction "VCC_4") (pintype "passive"))
      (node (ref "U6") (pin "4") (pinfunction "VCC_4") (pintype "passive"))
      (node (ref "U7") (pin "4") (pinfunction "VCC_4") (pintype "passive"))
      (node (ref "U8") (pin "4") (pinfunction "VCC_4") (pintype "passive"))
      (node (ref "U9") (pin "4") (pinfunction "VCC_4") (pintype "passive"))
    )
    (net (code "22") (name "12V_BATTIN") (class "Default")
      (node (ref "C8") (pin "2") (pinfunction "2_2") (pintype "passive"))
      (node (ref "C9") (pin "2") (pinfunction "2_2") (pintype "passive"))
      (node (ref "J2") (pin "36") (pinfunction "SYS_DCIN_36") (pintype "passive"))
      (node (ref "J2") (pin "38") (pinfunction "SYS_DCIN_38") (pintype "passive"))
      (node (ref "PWR1") (pin "1") (pinfunction "VPLUG_1") (pintype "passive"))
      (node (ref "R4") (pin "2") (pinfunction "2_2") (pintype "passive"))
      (node (ref "R5") (pin "1") (pinfunction "1_1") (pintype "passive"))
      (node (ref "U2") (pin "1") (pinfunction "VIN_1") (pintype "passive"))
    )
    (net (code "23") (name "GND") (class "Default")
      (node (ref "C1") (pin "2") (pinfunction "2_2") (pintype "passive"))
      (node (ref "C10") (pin "1") (pinfunction "1_1") (pintype "passive"))
      (node (ref "C11") (pin "1") (pinfunction "1_1") (pintype "passive"))
      (node (ref "C12") (pin "1") (pinfunction "1_1") (pintype "passive"))
      (node (ref "C13") (pin "1") (pinfunction "1_1") (pintype "passive"))
      (node (ref "C14") (pin "1") (pinfunction "1_1") (pintype "passive"))
      (node (ref "C15") (pin "1") (pinfunction "1_1") (pintype "passive"))
      (node (ref "C16") (pin "1") (pinfunction "1_1") (pintype "passive"))
      (node (ref "C17") (pin "1") (pinfunction "1_1") (pintype "passive"))
      (node (ref "C18") (pin "1") (pinfunction "1_1") (pintype "passive"))
      (node (ref "C19") (pin "1") (pinfunction "1_1") (pintype "passive"))
      (node (ref "C2") (pin "1") (pinfunction "1_1") (pintype "passive"))
      (node (ref "C20") (pin "1") (pinfunction "1_1") (pintype "passive"))
      (node (ref "C21") (pin "1") (pinfunction "1_1") (pintype "passive"))
      (node (ref "C22") (pin "1") (pinfunction "1_1") (pintype "passive"))
      (node (ref "C23") (pin "1") (pinfunction "1_1") (pintype "passive"))
      (node (ref "C24") (pin "1") (pinfunction "1_1") (pintype "passive"))
      (node (ref "C25") (pin "1") (pinfunction "1_1") (pintype "passive"))
      (node (ref "C26") (pin "1") (pinfunction "1_1") (pintype "passive"))
      (node (ref "C27") (pin "1") (pinfunction "1_1") (pintype "passive"))
      (node (ref "C28") (pin "1") (pinfunction "1_1") (pintype "passive"))
      (node (ref "C29") (pin "1") (pinfunction "1_1") (pintype "passive"))
      (node (ref "C30") (pin "1") (pinfunction "1_1") (pintype "passive"))
      (node (ref "C31") (pin "1") (pinfunction "1_1") (pintype "passive"))
      (node (ref "C32") (pin "1") (pinfunction "1_1") (pintype "passive"))
      (node (ref "C33") (pin "1") (pinfunction "1_1") (pintype "passive"))
      (node (ref "C6") (pin "1") (pinfunction "1_1") (pintype "passive"))
      (node (ref "C7") (pin "1") (pinfunction "1_1") (pintype "passive"))
      (node (ref "C8") (pin "1") (pinfunction "1_1") (pintype "passive"))
      (node (ref "C9") (pin "1") (pinfunction "1_1") (pintype "passive"))
      (node (ref "J1") (pin "12") (pinfunction "GND_12") (pintype "passive"))
      (node (ref "J1") (pin "13") (pinfunction "GND_13") (pintype "passive"))
      (node (ref "J1") (pin "18") (pinfunction "GND_18") (pintype "passive"))
      (node (ref "J1") (pin "19") (pinfunction "GND_19") (pintype "passive"))
      (node (ref "J1") (pin "24") (pinfunction "GND_24") (pintype "passive"))
      (node (ref "J1") (pin "25") (pinfunction "GND_25") (pintype "passive"))
      (node (ref "J1") (pin "30") (pinfunction "GND_30") (pintype "passive"))
      (node (ref "J1") (pin "31") (pinfunction "GND_31") (pintype "passive"))
      (node (ref "J1") (pin "37") (pinfunction "GND_37") (pintype "passive"))
      (node (ref "J1") (pin "40") (pinfunction "GND_40") (pintype "passive"))
      (node (ref "J1") (pin "43") (pinfunction "GND_43") (pintype "passive"))
      (node (ref "J1") (pin "46") (pinfunction "GND_46") (pintype "passive"))
      (node (ref "J1") (pin "49") (pinfunction "GND_49") (pintype "passive"))
      (node (ref "J1") (pin "52") (pinfunction "GND_52") (pintype "passive"))
      (node (ref "J1") (pin "55") (pinfunction "GND_55") (pintype "passive"))
      (node (ref "J1") (pin "58") (pinfunction "GND_58") (pintype "passive"))
      (node (ref "J1") (pin "6") (pinfunction "GND_6") (pintype "passive"))
      (node (ref "J2") (pin "1") (pinfunction "GND_1") (pintype "passive"))
      (node (ref "J2") (pin "2") (pinfunction "GND_2") (pintype "passive"))
      (node (ref "J2") (pin "39") (pinfunction "GND_39") (pintype "passive"))
      (node (ref "J2") (pin "40") (pinfunction "GND_40") (pintype "passive"))
      (node (ref "J3") (pin "4") (pinfunction "GND_4") (pintype "passive"))
      (node (ref "LCD1") (pin "10") (pinfunction "Gnd_10") (pintype "passive"))
      (node (ref "PWR1") (pin "2") (pinfunction "GND_2") (pintype "passive"))
      (node (ref "PWR1") (pin "3") (pinfunction "BREAK_3") (pintype "passive"))
      (node (ref "R3") (pin "2") (pinfunction "2_2") (pintype "passive"))
      (node (ref "R6") (pin "1") (pinfunction "1_1") (pintype "passive"))
      (node (ref "ROT1") (pin "2") (pinfunction "GND_2") (pintype "passive"))
      (node (ref "SW1") (pin "2") (pinfunction "2_2") (pintype "passive"))
      (node (ref "U1") (pin "11") (pinfunction "GND_11") (pintype "passive"))
      (node (ref "U10") (pin "3") (pinfunction "GND_3") (pintype "passive"))
      (node (ref "U11") (pin "3") (pinfunction "GND_3") (pintype "passive"))
      (node (ref "U12") (pin "3") (pinfunction "GND_3") (pintype "passive"))
      (node (ref "U13") (pin "3") (pinfunction "GND_3") (pintype "passive"))
      (node (ref "U14") (pin "3") (pinfunction "GND_3") (pintype "passive"))
      (node (ref "U15") (pin "3") (pinfunction "GND_3") (pintype "passive"))
      (node (ref "U16") (pin "3") (pinfunction "GND_3") (pintype "passive"))
      (node (ref "U17") (pin "3") (pinfunction "GND_3") (pintype "passive"))
      (node (ref "U18") (pin "3") (pinfunction "GND_3") (pintype "passive"))
      (node (ref "U19") (pin "3") (pinfunction "GND_3") (pintype "passive"))
      (node (ref "U2") (pin "4") (pinfunction "GND_4") (pintype "passive"))
      (node (ref "U2") (pin "8") (pinfunction "EP_8") (pintype "passive"))
      (node (ref "U20") (pin "3") (pinfunction "GND_3") (pintype "passive"))
      (node (ref "U21") (pin "3") (pinfunction "GND_3") (pintype "passive"))
      (node (ref "U22") (pin "3") (pinfunction "GND_3") (pintype "passive"))
      (node (ref "U23") (pin "3") (pinfunction "GND_3") (pintype "passive"))
      (node (ref "U24") (pin "2") (pinfunction "GND_2") (pintype "passive"))
      (node (ref "U24") (pin "3") (pinfunction "I0_3") (pintype "passive"))
      (node (ref "U3") (pin "3") (pinfunction "GND_3") (pintype "passive"))
      (node (ref "U4") (pin "3") (pinfunction "GND_3") (pintype "passive"))
      (node (ref "U5") (pin "3") (pinfunction "GND_3") (pintype "passive"))
      (node (ref "U6") (pin "3") (pinfunction "GND_3") (pintype "passive"))
      (node (ref "U7") (pin "3") (pinfunction "GND_3") (pintype "passive"))
      (node (ref "U8") (pin "3") (pinfunction "GND_3") (pintype "passive"))
      (node (ref "U9") (pin "3") (pinfunction "GND_3") (pintype "passive"))
    )
    (net (code "24") (name "LS_EXP_1P8") (class "Default")
      (node (ref "C1") (pin "1") (pinfunction "1_1") (pintype "passive"))
      (node (ref "J2") (pin "35") (pinfunction "LS_EXP_1P8_35") (pintype "passive"))
      (node (ref "U1") (pin "10") (pinfunction "OE_10") (pintype "passive"))
      (node (ref "U1") (pin "2") (pinfunction "Vcca_2") (pintype "passive"))
    )
    (net (code "25") (name "Net-(J3-SPKR+)") (class "Default")
      (node (ref "J3") (pin "1") (pinfunction "SPKR+_1") (pintype "passive"))
      (node (ref "SPKR1") (pin "1") (pinfunction "Red+_1") (pintype "passive"))
    )
    (net (code "26") (name "Net-(J3-SPKR-)") (class "Default")
      (node (ref "J3") (pin "2") (pinfunction "SPKR-_2") (pintype "passive"))
      (node (ref "SPKR1") (pin "2") (pinfunction "Black-_2") (pintype "passive"))
    )
    (net (code "27") (name "Net-(ROT1-CHA)") (class "Default")
      (node (ref "R10") (pin "2") (pinfunction "2_2") (pintype "passive"))
      (node (ref "R8") (pin "1") (pinfunction "1_1") (pintype "passive"))
      (node (ref "ROT1") (pin "1") (pinfunction "CHA_1") (pintype "passive"))
    )
    (net (code "28") (name "Net-(ROT1-CHB)") (class "Default")
      (node (ref "R11") (pin "2") (pinfunction "2_2") (pintype "passive"))
      (node (ref "R9") (pin "1") (pinfunction "1_1") (pintype "passive"))
      (node (ref "ROT1") (pin "3") (pinfunction "CHB_3") (pintype "passive"))
    )
    (net (code "29") (name "Net-(U3-CO)") (class "Default")
      (node (ref "U3") (pin "5") (pinfunction "CO_5") (pintype "passive"))
      (node (ref "U4") (pin "2") (pinfunction "CI_2") (pintype "passive"))
    )
    (net (code "30") (name "Net-(U3-DO)") (class "Default")
      (node (ref "U3") (pin "6") (pinfunction "DO_6") (pintype "passive"))
      (node (ref "U4") (pin "1") (pinfunction "DI_1") (pintype "passive"))
    )
    (net (code "31") (name "Net-(U4-CO)") (class "Default")
      (node (ref "U4") (pin "5") (pinfunction "CO_5") (pintype "passive"))
      (node (ref "U5") (pin "2") (pinfunction "CI_2") (pintype "passive"))
    )
    (net (code "32") (name "Net-(U4-DO)") (class "Default")
      (node (ref "U4") (pin "6") (pinfunction "DO_6") (pintype "passive"))
      (node (ref "U5") (pin "1") (pinfunction "DI_1") (pintype "passive"))
    )
    (net (code "33") (name "Net-(U5-CO)") (class "Default")
      (node (ref "U5") (pin "5") (pinfunction "CO_5") (pintype "passive"))
      (node (ref "U6") (pin "2") (pinfunction "CI_2") (pintype "passive"))
    )
    (net (code "34") (name "Net-(U5-DO)") (class "Default")
      (node (ref "U5") (pin "6") (pinfunction "DO_6") (pintype "passive"))
      (node (ref "U6") (pin "1") (pinfunction "DI_1") (pintype "passive"))
    )
    (net (code "35") (name "Net-(U6-CO)") (class "Default")
      (node (ref "U6") (pin "5") (pinfunction "CO_5") (pintype "passive"))
      (node (ref "U7") (pin "2") (pinfunction "CI_2") (pintype "passive"))
    )
    (net (code "36") (name "Net-(U6-DO)") (class "Default")
      (node (ref "U6") (pin "6") (pinfunction "DO_6") (pintype "passive"))
      (node (ref "U7") (pin "1") (pinfunction "DI_1") (pintype "passive"))
    )
    (net (code "37") (name "Net-(U7-CO)") (class "Default")
      (node (ref "U7") (pin "5") (pinfunction "CO_5") (pintype "passive"))
      (node (ref "U8") (pin "2") (pinfunction "CI_2") (pintype "passive"))
    )
    (net (code "38") (name "Net-(U7-DO)") (class "Default")
      (node (ref "U7") (pin "6") (pinfunction "DO_6") (pintype "passive"))
      (node (ref "U8") (pin "1") (pinfunction "DI_1") (pintype "passive"))
    )
    (net (code "39") (name "Net-(U8-CO)") (class "Default")
      (node (ref "U8") (pin "5") (pinfunction "CO_5") (pintype "passive"))
      (node (ref "U9") (pin "2") (pinfunction "CI_2") (pintype "passive"))
    )
    (net (code "40") (name "Net-(U8-DO)") (class "Default")
      (node (ref "U8") (pin "6") (pinfunction "DO_6") (pintype "passive"))
      (node (ref "U9") (pin "1") (pinfunction "DI_1") (pintype "passive"))
    )
    (net (code "41") (name "Net-(U10-CI)") (class "Default")
      (node (ref "U10") (pin "2") (pinfunction "CI_2") (pintype "passive"))
      (node (ref "U9") (pin "5") (pinfunction "CO_5") (pintype "passive"))
    )
    (net (code "42") (name "Net-(U10-CO)") (class "Default")
      (node (ref "U10") (pin "5") (pinfunction "CO_5") (pintype "passive"))
      (node (ref "U11") (pin "2") (pinfunction "CI_2") (pintype "passive"))
    )
    (net (code "43") (name "Net-(U10-DI)") (class "Default")
      (node (ref "U10") (pin "1") (pinfunction "DI_1") (pintype "passive"))
      (node (ref "U9") (pin "6") (pinfunction "DO_6") (pintype "passive"))
    )
    (net (code "44") (name "Net-(U10-DO)") (class "Default")
      (node (ref "U10") (pin "6") (pinfunction "DO_6") (pintype "passive"))
      (node (ref "U11") (pin "1") (pinfunction "DI_1") (pintype "passive"))
    )
    (net (code "45") (name "Net-(U11-CO)") (class "Default")
      (node (ref "U11") (pin "5") (pinfunction "CO_5") (pintype "passive"))
      (node (ref "U12") (pin "2") (pinfunction "CI_2") (pintype "passive"))
    )
    (net (code "46") (name "Net-(U11-DO)") (class "Default")
      (node (ref "U11") (pin "6") (pinfunction "DO_6") (pintype "passive"))
      (node (ref "U12") (pin "1") (pinfunction "DI_1") (pintype "passive"))
    )
    (net (code "47") (name "Net-(U12-CO)") (class "Default")
      (node (ref "U12") (pin "5") (pinfunction "CO_5") (pintype "passive"))
      (node (ref "U22") (pin "2") (pinfunction "CI_2") (pintype "passive"))
    )
    (net (code "48") (name "Net-(U12-DO)") (class "Default")
      (node (ref "U12") (pin "6") (pinfunction "DO_6") (pintype "passive"))
      (node (ref "U22") (pin "1") (pinfunction "DI_1") (pintype "passive"))
    )
    (net (code "49") (name "Net-(U13-CI)") (class "Default")
      (node (ref "U13") (pin "2") (pinfunction "CI_2") (pintype "passive"))
      (node (ref "U14") (pin "5") (pinfunction "CO_5") (pintype "passive"))
    )
    (net (code "50") (name "Net-(U13-DI)") (class "Default")
      (node (ref "U13") (pin "1") (pinfunction "DI_1") (pintype "passive"))
      (node (ref "U14") (pin "6") (pinfunction "DO_6") (pintype "passive"))
    )
    (net (code "51") (name "Net-(U14-CI)") (class "Default")
      (node (ref "U14") (pin "2") (pinfunction "CI_2") (pintype "passive"))
      (node (ref "U15") (pin "5") (pinfunction "CO_5") (pintype "passive"))
    )
    (net (code "52") (name "Net-(U14-DI)") (class "Default")
      (node (ref "U14") (pin "1") (pinfunction "DI_1") (pintype "passive"))
      (node (ref "U15") (pin "6") (pinfunction "DO_6") (pintype "passive"))
    )
    (net (code "53") (name "Net-(U15-CI)") (class "Default")
      (node (ref "U15") (pin "2") (pinfunction "CI_2") (pintype "passive"))
      (node (ref "U16") (pin "5") (pinfunction "CO_5") (pintype "passive"))
    )
    (net (code "54") (name "Net-(U15-DI)") (class "Default")
      (node (ref "U15") (pin "1") (pinfunction "DI_1") (pintype "passive"))
      (node (ref "U16") (pin "6") (pinfunction "DO_6") (pintype "passive"))
    )
    (net (code "55") (name "Net-(U16-CI)") (class "Default")
      (node (ref "U16") (pin "2") (pinfunction "CI_2") (pintype "passive"))
      (node (ref "U17") (pin "5") (pinfunction "CO_5") (pintype "passive"))
    )
    (net (code "56") (name "Net-(U16-DI)") (class "Default")
      (node (ref "U16") (pin "1") (pinfunction "DI_1") (pintype "passive"))
      (node (ref "U17") (pin "6") (pinfunction "DO_6") (pintype "passive"))
    )
    (net (code "57") (name "Net-(U17-CI)") (class "Default")
      (node (ref "U17") (pin "2") (pinfunction "CI_2") (pintype "passive"))
      (node (ref "U18") (pin "5") (pinfunction "CO_5") (pintype "passive"))
    )
    (net (code "58") (name "Net-(U17-DI)") (class "Default")
      (node (ref "U17") (pin "1") (pinfunction "DI_1") (pintype "passive"))
      (node (ref "U18") (pin "6") (pinfunction "DO_6") (pintype "passive"))
    )
    (net (code "59") (name "Net-(U18-CI)") (class "Default")
      (node (ref "U18") (pin "2") (pinfunction "CI_2") (pintype "passive"))
      (node (ref "U19") (pin "5") (pinfunction "CO_5") (pintype "passive"))
    )
    (net (code "60") (name "Net-(U18-DI)") (class "Default")
      (node (ref "U18") (pin "1") (pinfunction "DI_1") (pintype "passive"))
      (node (ref "U19") (pin "6") (pinfunction "DO_6") (pintype "passive"))
    )
    (net (code "61") (name "Net-(U19-CI)") (class "Default")
      (node (ref "U19") (pin "2") (pinfunction "CI_2") (pintype "passive"))
      (node (ref "U20") (pin "5") (pinfunction "CO_5") (pintype "passive"))
    )
    (net (code "62") (name "Net-(U19-DI)") (class "Default")
      (node (ref "U19") (pin "1") (pinfunction "DI_1") (pintype "passive"))
      (node (ref "U20") (pin "6") (pinfunction "DO_6") (pintype "passive"))
    )
    (net (code "63") (name "Net-(U20-CI)") (class "Default")
      (node (ref "U20") (pin "2") (pinfunction "CI_2") (pintype "passive"))
      (node (ref "U21") (pin "5") (pinfunction "CO_5") (pintype "passive"))
    )
    (net (code "64") (name "Net-(U20-DI)") (class "Default")
      (node (ref "U20") (pin "1") (pinfunction "DI_1") (pintype "passive"))
      (node (ref "U21") (pin "6") (pinfunction "DO_6") (pintype "passive"))
    )
    (net (code "65") (name "Net-(U21-CI)") (class "Default")
      (node (ref "U21") (pin "2") (pinfunction "CI_2") (pintype "passive"))
      (node (ref "U22") (pin "5") (pinfunction "CO_5") (pintype "passive"))
    )
    (net (code "66") (name "Net-(U21-DI)") (class "Default")
      (node (ref "U21") (pin "1") (pinfunction "DI_1") (pintype "passive"))
      (node (ref "U22") (pin "6") (pinfunction "DO_6") (pintype "passive"))
    )
    (net (code "67") (name "Net-(U23-A)") (class "Default")
      (node (ref "R7") (pin "1") (pinfunction "1_1") (pintype "passive"))
      (node (ref "SW1") (pin "1") (pinfunction "1_1") (pintype "passive"))
      (node (ref "U23") (pin "2") (pinfunction "A_2") (pintype "passive"))
    )
    (net (code "68") (name "Net-(U24-Z)") (class "Default")
      (node (ref "U24") (pin "4") (pinfunction "Z_4") (pintype "passive"))
      (node (ref "U3") (pin "2") (pinfunction "CI_2") (pintype "passive"))
    )
    (net (code "69") (name "unconnected-(J1-CSI0_MCLK-Pad15)") (class "Default")
      (node (ref "J1") (pin "15") (pinfunction "CSI0_MCLK_15") (pintype "passive+no_connect"))
    )
    (net (code "70") (name "unconnected-(J1-CSI1_MCLK-Pad17)") (class "Default")
      (node (ref "J1") (pin "17") (pinfunction "CSI1_MCLK_17") (pintype "passive+no_connect"))
    )
    (net (code "71") (name "unconnected-(J1-I2C2_SCL-Pad32)") (class "Default")
      (node (ref "J1") (pin "32") (pinfunction "I2C2_SCL_32") (pintype "passive+no_connect"))
    )
    (net (code "72") (name "unconnected-(J1-I2C2_SDA-Pad34)") (class "Default")
      (node (ref "J1") (pin "34") (pinfunction "I2C2_SDA_34") (pintype "passive+no_connect"))
    )
    (net (code "73") (name "unconnected-(J1-I2C3_SCL-Pad36)") (class "Default")
      (node (ref "J1") (pin "36") (pinfunction "I2C3_SCL_36") (pintype "passive+no_connect"))
    )
    (net (code "74") (name "unconnected-(J1-I2C3_SDA-Pad38)") (class "Default")
      (node (ref "J1") (pin "38") (pinfunction "I2C3_SDA_38") (pintype "passive+no_connect"))
    )
    (net (code "75") (name "unconnected-(J1-MIPI_CSI0_CLK_M-Pad4)") (class "Default")
      (node (ref "J1") (pin "4") (pinfunction "MIPI_CSI0_CLK_M_4") (pintype "passive+no_connect"))
    )
    (net (code "76") (name "unconnected-(J1-MIPI_CSI0_CLK_P-Pad2)") (class "Default")
      (node (ref "J1") (pin "2") (pinfunction "MIPI_CSI0_CLK_P_2") (pintype "passive+no_connect"))
    )
    (net (code "77") (name "unconnected-(J1-MIPI_CSI0_DATA0_M-Pad10)") (class "Default")
      (node (ref "J1") (pin "10") (pinfunction "MIPI_CSI0_DATA0_M_10") (pintype "passive+no_connect"))
    )
    (net (code "78") (name "unconnected-(J1-MIPI_CSI0_DATA0_P-Pad8)") (class "Default")
      (node (ref "J1") (pin "8") (pinfunction "MIPI_CSI0_DATA0_P_8") (pintype "passive+no_connect"))
    )
    (net (code "79") (name "unconnected-(J1-MIPI_CSI0_DATA1_M-Pad16)") (class "Default")
      (node (ref "J1") (pin "16") (pinfunction "MIPI_CSI0_DATA1_M_16") (pintype "passive+no_connect"))
    )
    (net (code "80") (name "unconnected-(J1-MIPI_CSI0_DATA1_P-Pad14)") (class "Default")
      (node (ref "J1") (pin "14") (pinfunction "MIPI_CSI0_DATA1_P_14") (pintype "passive+no_connect"))
    )
    (net (code "81") (name "unconnected-(J1-MIPI_CSI0_DATA2_M-Pad22)") (class "Default")
      (node (ref "J1") (pin "22") (pinfunction "MIPI_CSI0_DATA2_M_22") (pintype "passive+no_connect"))
    )
    (net (code "82") (name "unconnected-(J1-MIPI_CSI0_DATA2_P-Pad20)") (class "Default")
      (node (ref "J1") (pin "20") (pinfunction "MIPI_CSI0_DATA2_P_20") (pintype "passive+no_connect"))
    )
    (net (code "83") (name "unconnected-(J1-MIPI_CSI0_DATA3_M-Pad28)") (class "Default")
      (node (ref "J1") (pin "28") (pinfunction "MIPI_CSI0_DATA3_M_28") (pintype "passive+no_connect"))
    )
    (net (code "84") (name "unconnected-(J1-MIPI_CSI0_DATA3_P-Pad26)") (class "Default")
      (node (ref "J1") (pin "26") (pinfunction "MIPI_CSI0_DATA3_P_26") (pintype "passive+no_connect"))
    )
    (net (code "85") (name "unconnected-(J1-MIPI_CSI1_CLK_M-Pad56)") (class "Default")
      (node (ref "J1") (pin "56") (pinfunction "MIPI_CSI1_CLK_M_56") (pintype "passive+no_connect"))
    )
    (net (code "86") (name "unconnected-(J1-MIPI_CSI1_CLK_P-Pad54)") (class "Default")
      (node (ref "J1") (pin "54") (pinfunction "MIPI_CSI1_CLK_P_54") (pintype "passive+no_connect"))
    )
    (net (code "87") (name "unconnected-(J1-MIPI_CSI1_DATA0_M-Pad44)") (class "Default")
      (node (ref "J1") (pin "44") (pinfunction "MIPI_CSI1_DATA0_M_44") (pintype "passive+no_connect"))
    )
    (net (code "88") (name "unconnected-(J1-MIPI_CSI1_DATA0_M-Pad50)") (class "Default")
      (node (ref "J1") (pin "50") (pinfunction "MIPI_CSI1_DATA0_M_50") (pintype "passive+no_connect"))
    )
    (net (code "89") (name "unconnected-(J1-MIPI_CSI1_DATA0_P-Pad42)") (class "Default")
      (node (ref "J1") (pin "42") (pinfunction "MIPI_CSI1_DATA0_P_42") (pintype "passive+no_connect"))
    )
    (net (code "90") (name "unconnected-(J1-MIPI_CSI1_DATA1_P-Pad48)") (class "Default")
      (node (ref "J1") (pin "48") (pinfunction "MIPI_CSI1_DATA1_P_48") (pintype "passive+no_connect"))
    )
    (net (code "91") (name "unconnected-(J1-MIPI_DSI0_CLK_M_EXP_CONN-Pad23)") (class "Default")
      (node (ref "J1") (pin "23") (pinfunction "MIPI_DSI0_CLK_M_EXP_CONN_23") (pintype "passive+no_connect"))
    )
    (net (code "92") (name "unconnected-(J1-MIPI_DSI0_CLK_P_EXP_CONN-Pad21)") (class "Default")
      (node (ref "J1") (pin "21") (pinfunction "MIPI_DSI0_CLK_P_EXP_CONN_21") (pintype "passive+no_connect"))
    )
    (net (code "93") (name "unconnected-(J1-MIPI_DSI0_DATA0_M_EXP_CONN-Pad29)") (class "Default")
      (node (ref "J1") (pin "29") (pinfunction "MIPI_DSI0_DATA0_M_EXP_CONN_29") (pintype "passive+no_connect"))
    )
    (net (code "94") (name "unconnected-(J1-MIPI_DSI0_DATA0_P_EXP_CONN-Pad27)") (class "Default")
      (node (ref "J1") (pin "27") (pinfunction "MIPI_DSI0_DATA0_P_EXP_CONN_27") (pintype "passive+no_connect"))
    )
    (net (code "95") (name "unconnected-(J1-MIPI_DSI0_DATA1_M_EXP_CONN-Pad35)") (class "Default")
      (node (ref "J1") (pin "35") (pinfunction "MIPI_DSI0_DATA1_M_EXP_CONN_35") (pintype "passive+no_connect"))
    )
    (net (code "96") (name "unconnected-(J1-MIPI_DSI0_DATA1_P_EXP_CONN-Pad33)") (class "Default")
      (node (ref "J1") (pin "33") (pinfunction "MIPI_DSI0_DATA1_P_EXP_CONN_33") (pintype "passive+no_connect"))
    )
    (net (code "97") (name "unconnected-(J1-MIPI_DSI0_DATA2_M_EXP_CONN-Pad41)") (class "Default")
      (node (ref "J1") (pin "41") (pinfunction "MIPI_DSI0_DATA2_M_EXP_CONN_41") (pintype "passive+no_connect"))
    )
    (net (code "98") (name "unconnected-(J1-MIPI_DSI0_DATA2_P_EXP_CONN-Pad39)") (class "Default")
      (node (ref "J1") (pin "39") (pinfunction "MIPI_DSI0_DATA2_P_EXP_CONN_39") (pintype "passive+no_connect"))
    )
    (net (code "99") (name "unconnected-(J1-MIPI_DSI0_DATA3_M_EXP_CONN-Pad47)") (class "Default")
      (node (ref "J1") (pin "47") (pinfunction "MIPI_DSI0_DATA3_M_EXP_CONN_47") (pintype "passive+no_connect"))
    )
    (net (code "100") (name "unconnected-(J1-MIPI_DSI0_DATA3_P_EXP_CONN-Pad45)") (class "Default")
      (node (ref "J1") (pin "45") (pinfunction "MIPI_DSI0_DATA3_P_EXP_CONN_45") (pintype "passive+no_connect"))
    )
    (net (code "101") (name "unconnected-(J1-N.C.-Pad3)") (class "Default")
      (node (ref "J1") (pin "3") (pinfunction "N.C._3") (pintype "passive+no_connect"))
    )
    (net (code "102") (name "unconnected-(J1-N.C.-Pad5)") (class "Default")
      (node (ref "J1") (pin "5") (pinfunction "N.C._5") (pintype "passive+no_connect"))
    )
    (net (code "103") (name "unconnected-(J1-N.C.-Pad57)") (class "Default")
      (node (ref "J1") (pin "57") (pinfunction "N.C._57") (pintype "passive+no_connect"))
    )
    (net (code "104") (name "unconnected-(J1-N.C.-Pad59)") (class "Default")
      (node (ref "J1") (pin "59") (pinfunction "N.C._59") (pintype "passive+no_connect"))
    )
    (net (code "105") (name "unconnected-(J1-N.C.-Pad60)") (class "Default")
      (node (ref "J1") (pin "60") (pinfunction "N.C._60") (pintype "passive+no_connect"))
    )
    (net (code "106") (name "unconnected-(J1-SPI1_CLK-Pad9)") (class "Default")
      (node (ref "J1") (pin "9") (pinfunction "SPI1_CLK_9") (pintype "passive+no_connect"))
    )
    (net (code "107") (name "unconnected-(J1-SPI1_CS_N-Pad7)") (class "Default")
      (node (ref "J1") (pin "7") (pinfunction "SPI1_CS_N_7") (pintype "passive+no_connect"))
    )
    (net (code "108") (name "unconnected-(J1-SPI1_MISO-Pad11)") (class "Default")
      (node (ref "J1") (pin "11") (pinfunction "SPI1_MISO_11") (pintype "passive+no_connect"))
    )
    (net (code "109") (name "unconnected-(J1-SPI1_MOSI-Pad1)") (class "Default")
      (node (ref "J1") (pin "1") (pinfunction "SPI1_MOSI_1") (pintype "passive+no_connect"))
    )
    (net (code "110") (name "unconnected-(J1-USB_HS_D_M_EXP-Pad53)") (class "Default")
      (node (ref "J1") (pin "53") (pinfunction "USB_HS_D_M_EXP_53") (pintype "passive+no_connect"))
    )
    (net (code "111") (name "unconnected-(J1-USB_HS_D_P_EXP-Pad51)") (class "Default")
      (node (ref "J1") (pin "51") (pinfunction "USB_HS_D_P_EXP_51") (pintype "passive+no_connect"))
    )
    (net (code "112") (name "unconnected-(J2-I2C0_SCL-Pad15)") (class "Default")
      (node (ref "J2") (pin "15") (pinfunction "I2C0_SCL_15") (pintype "passive+no_connect"))
    )
    (net (code "113") (name "unconnected-(J2-I2C0_SDA-Pad17)") (class "Default")
      (node (ref "J2") (pin "17") (pinfunction "I2C0_SDA_17") (pintype "passive+no_connect"))
    )
    (net (code "114") (name "unconnected-(J2-I2C1_SCL-Pad19)") (class "Default")
      (node (ref "J2") (pin "19") (pinfunction "I2C1_SCL_19") (pintype "passive+no_connect"))
    )
    (net (code "115") (name "unconnected-(J2-I2C1_SDA-Pad21)") (class "Default")
      (node (ref "J2") (pin "21") (pinfunction "I2C1_SDA_21") (pintype "passive+no_connect"))
    )
    (net (code "116") (name "unconnected-(J2-LS_EXP_GPIO_A-Pad23)") (class "Default")
      (node (ref "J2") (pin "23") (pinfunction "LS_EXP_GPIO_A_23") (pintype "passive+no_connect"))
    )
    (net (code "117") (name "unconnected-(J2-LS_EXP_GPIO_C-Pad25)") (class "Default")
      (node (ref "J2") (pin "25") (pinfunction "LS_EXP_GPIO_C_25") (pintype "passive+no_connect"))
    )
    (net (code "118") (name "unconnected-(J2-LS_EXP_GPIO_E-Pad27)") (class "Default")
      (node (ref "J2") (pin "27") (pinfunction "LS_EXP_GPIO_E_27") (pintype "passive+no_connect"))
    )
    (net (code "119") (name "unconnected-(J2-LS_EXP_GPIO_F-Pad28)") (class "Default")
      (node (ref "J2") (pin "28") (pinfunction "LS_EXP_GPIO_F_28") (pintype "passive+no_connect"))
    )
    (net (code "120") (name "unconnected-(J2-LS_EXP_GPIO_G-Pad29)") (class "Default")
      (node (ref "J2") (pin "29") (pinfunction "LS_EXP_GPIO_G_29") (pintype "passive+no_connect"))
    )
    (net (code "121") (name "unconnected-(J2-LS_EXP_GPIO_H-Pad30)") (class "Default")
      (node (ref "J2") (pin "30") (pinfunction "LS_EXP_GPIO_H_30") (pintype "passive+no_connect"))
    )
    (net (code "122") (name "unconnected-(J2-LS_EXP_MI2S_DATA0-Pad20)") (class "Default")
      (node (ref "J2") (pin "20") (pinfunction "LS_EXP_MI2S_DATA0_20") (pintype "passive+no_connect"))
    )
    (net (code "123") (name "unconnected-(J2-LS_EXP_MI2S_SCK-Pad18)") (class "Default")
      (node (ref "J2") (pin "18") (pinfunction "LS_EXP_MI2S_SCK_18") (pintype "passive+no_connect"))
    )
    (net (code "124") (name "unconnected-(J2-LS_EXP_MI2S_WS-Pad16)") (class "Default")
      (node (ref "J2") (pin "16") (pinfunction "LS_EXP_MI2S_WS_16") (pintype "passive+no_connect"))
    )
    (net (code "125") (name "unconnected-(J2-N.C.-Pad22)") (class "Default")
      (node (ref "J2") (pin "22") (pinfunction "N.C._22") (pintype "passive+no_connect"))
    )
    (net (code "126") (name "unconnected-(J2-PHONE_ON_N-Pad4)") (class "Default")
      (node (ref "J2") (pin "4") (pinfunction "PHONE_ON_N_4") (pintype "passive+no_connect"))
    )
    (net (code "127") (name "unconnected-(J2-PM_RESIN_N-Pad6)") (class "Default")
      (node (ref "J2") (pin "6") (pinfunction "PM_RESIN_N_6") (pintype "passive+no_connect"))
    )
    (net (code "128") (name "unconnected-(J2-SPI0_CS_N-Pad12)") (class "Default")
      (node (ref "J2") (pin "12") (pinfunction "SPI0_CS_N_12") (pintype "output"))
    )
    (net (code "129") (name "unconnected-(J2-SPI0_MISO-Pad10)") (class "Default")
      (node (ref "J2") (pin "10") (pinfunction "SPI0_MISO_10") (pintype "passive"))
    )
    (net (code "130") (name "unconnected-(J2-SYS_5P0-Pad37)") (class "Default")
      (node (ref "J2") (pin "37") (pinfunction "SYS_5P0_37") (pintype "passive+no_connect"))
    )
    (net (code "131") (name "unconnected-(J2-UART0_CTS_N-Pad3)") (class "Default")
      (node (ref "J2") (pin "3") (pinfunction "UART0_CTS_N_3") (pintype "passive+no_connect"))
    )
    (net (code "132") (name "unconnected-(J2-UART0_RTS_N-Pad9)") (class "Default")
      (node (ref "J2") (pin "9") (pinfunction "UART0_RTS_N_9") (pintype "passive+no_connect"))
    )
    (net (code "133") (name "unconnected-(J2-UART0_RX-Pad7)") (class "Default")
      (node (ref "J2") (pin "7") (pinfunction "UART0_RX_7") (pintype "passive+no_connect"))
    )
    (net (code "134") (name "unconnected-(J2-UART0_TX-Pad5)") (class "Default")
      (node (ref "J2") (pin "5") (pinfunction "UART0_TX_5") (pintype "passive+no_connect"))
    )
    (net (code "135") (name "unconnected-(J2-UART1_RX-Pad13)") (class "Default")
      (node (ref "J2") (pin "13") (pinfunction "UART1_RX_13") (pintype "passive+no_connect"))
    )
    (net (code "136") (name "unconnected-(J2-UART1_TX-Pad11)") (class "Default")
      (node (ref "J2") (pin "11") (pinfunction "UART1_TX_11") (pintype "passive+no_connect"))
    )
    (net (code "137") (name "unconnected-(J3-CDC_GND_FILT-Pad5)") (class "Default")
      (node (ref "J3") (pin "5") (pinfunction "CDC_GND_FILT_5") (pintype "passive+no_connect"))
    )
    (net (code "138") (name "unconnected-(J3-CDC_HPH_L-Pad10)") (class "Default")
      (node (ref "J3") (pin "10") (pinfunction "CDC_HPH_L_10") (pintype "passive+no_connect"))
    )
    (net (code "139") (name "unconnected-(J3-CDC_HPH_R-Pad8)") (class "Default")
      (node (ref "J3") (pin "8") (pinfunction "CDC_HPH_R_8") (pintype "passive+no_connect"))
    )
    (net (code "140") (name "unconnected-(J3-CDC_HPH_REF-Pad9)") (class "Default")
      (node (ref "J3") (pin "9") (pinfunction "CDC_HPH_REF_9") (pintype "passive+no_connect"))
    )
    (net (code "141") (name "unconnected-(J3-CDC_HS_DET-Pad11)") (class "Default")
      (node (ref "J3") (pin "11") (pinfunction "CDC_HS_DET_11") (pintype "passive+no_connect"))
    )
    (net (code "142") (name "unconnected-(J3-CDC_MIC2_P-Pad6)") (class "Default")
      (node (ref "J3") (pin "6") (pinfunction "CDC_MIC2_P_6") (pintype "passive+no_connect"))
    )
    (net (code "143") (name "unconnected-(J3-CDC_MIC3_P-Pad7)") (class "Default")
      (node (ref "J3") (pin "7") (pinfunction "CDC_MIC3_P_7") (pintype "passive+no_connect"))
    )
    (net (code "144") (name "unconnected-(J3-CDC_MIC_BIAS1-Pad12)") (class "Default")
      (node (ref "J3") (pin "12") (pinfunction "CDC_MIC_BIAS1_12") (pintype "passive+no_connect"))
    )
    (net (code "145") (name "unconnected-(J3-FM_RX_ANT-Pad15)") (class "Default")
      (node (ref "J3") (pin "15") (pinfunction "FM_RX_ANT_15") (pintype "passive+no_connect"))
    )
    (net (code "146") (name "unconnected-(J3-N.C.-Pad13)") (class "Default")
      (node (ref "J3") (pin "13") (pinfunction "N.C._13") (pintype "passive+no_connect"))
    )
    (net (code "147") (name "unconnected-(J3-N.C.-Pad14)") (class "Default")
      (node (ref "J3") (pin "14") (pinfunction "N.C._14") (pintype "passive+no_connect"))
    )
    (net (code "148") (name "unconnected-(J3-N.C.-Pad16)") (class "Default")
      (node (ref "J3") (pin "16") (pinfunction "N.C._16") (pintype "passive+no_connect"))
    )
    (net (code "149") (name "unconnected-(J3-VPH_PWR_3V7-Pad3)") (class "Default")
      (node (ref "J3") (pin "3") (pinfunction "VPH_PWR_3V7_3") (pintype "passive+no_connect"))
    )
    (net (code "150") (name "unconnected-(LCD1-CARD_CS-Pad6)") (class "Default")
      (node (ref "LCD1") (pin "6") (pinfunction "CARD_CS_6") (pintype "passive+no_connect"))
    )
    (net (code "151") (name "unconnected-(LCD1-MISO-Pad2)") (class "Default")
      (node (ref "LCD1") (pin "2") (pinfunction "MISO_2") (pintype "passive+no_connect"))
    )
    (net (code "152") (name "unconnected-(U13-CO-Pad5)") (class "Default")
      (node (ref "U13") (pin "5") (pinfunction "CO_5") (pintype "passive"))
    )
    (net (code "153") (name "unconnected-(U13-DO-Pad6)") (class "Default")
      (node (ref "U13") (pin "6") (pinfunction "DO_6") (pintype "passive"))
    )
    (net (code "154") (name "unconnected-(U23-NC-Pad1)") (class "Default")
      (node (ref "U23") (pin "1") (pinfunction "NC_1") (pintype "passive+no_connect"))
    )
  )
)
